# Si7020-A10_-_czujnik_wilgotno_ci.net
KiCad netlist of a schematic drawn in EAGLE
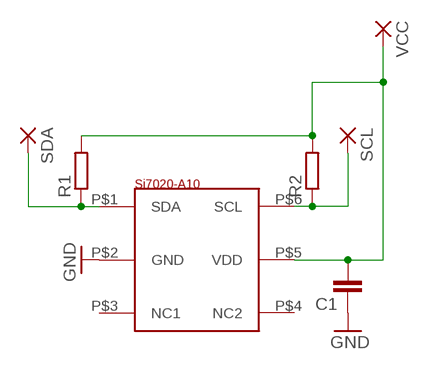
[diagram p0: schematic, sheet 1]

(export (version "E")
  (design (tool "Eeschema 10.0.6"))
  (components
    (comp (ref "C1")
      (value "C-EUC0805")
      (footprint "eagle-import:C0805")
      (libsource (lib "eagle-import") (part "C-EUC0805"))
    )
    (comp (ref "R1")
      (value "R-EU_M0805")
      (footprint "eagle-import:M0805")
      (libsource (lib "eagle-import") (part "R-EU_M0805"))
    )
    (comp (ref "R2")
      (value "R-EU_M0805")
      (footprint "eagle-import:M0805")
      (libsource (lib "eagle-import") (part "R-EU_M0805"))
    )
    (comp (ref "SCL")
      (value "2,54/0,9")
      (footprint "eagle-import:2,54_0,9")
      (libsource (lib "eagle-import") (part "2,54/0,9"))
    )
    (comp (ref "SDA")
      (value "2,54/0,9")
      (footprint "eagle-import:2,54_0,9")
      (libsource (lib "eagle-import") (part "2,54/0,9"))
    )
    (comp (ref "U$1")
      (value "SI7020-A10")
      (footprint "eagle-import:DFN6(3X3MM)")
      (libsource (lib "eagle-import") (part "SI7020-A10"))
    )
    (comp (ref "VCC")
      (value "2,54/0,9")
      (footprint "eagle-import:2,54_0,9")
      (libsource (lib "eagle-import") (part "2,54/0,9"))
    )
  )
  (nets
    (net (code "1") (name "GND") (class "Default")
      (node (ref "C1") (pin "1") (pinfunction "1_1") (pintype "passive"))
      (node (ref "U$1") (pin "P$2") (pinfunction "GND_P$2") (pintype "bidirectional"))
    )
    (net (code "2") (name "Net-(SCL-P)") (class "Default")
      (node (ref "R2") (pin "1") (pinfunction "1_1") (pintype "passive"))
      (node (ref "SCL") (pin "1") (pinfunction "P_1") (pintype "passive"))
      (node (ref "U$1") (pin "P$6") (pinfunction "SCL_P$6") (pintype "bidirectional"))
    )
    (net (code "3") (name "Net-(SDA-P)") (class "Default")
      (node (ref "R1") (pin "1") (pinfunction "1_1") (pintype "passive"))
      (node (ref "SDA") (pin "1") (pinfunction "P_1") (pintype "passive"))
      (node (ref "U$1") (pin "P$1") (pinfunction "SDA_P$1") (pintype "bidirectional"))
    )
    (net (code "4") (name "Net-(U$1-VDD)") (class "Default")
      (node (ref "C1") (pin "2") (pinfunction "2_2") (pintype "passive"))
      (node (ref "R1") (pin "2") (pinfunction "2_2") (pintype "passive"))
      (node (ref "R2") (pin "2") (pinfunction "2_2") (pintype "passive"))
      (node (ref "U$1") (pin "P$5") (pinfunction "VDD_P$5") (pintype "bidirectional"))
      (node (ref "VCC") (pin "1") (pinfunction "P_1") (pintype "passive"))
    )
    (net (code "5") (name "unconnected-(U$1-NC1-PadP$3)") (class "Default")
      (node (ref "U$1") (pin "P$3") (pinfunction "NC1_P$3") (pintype "bidirectional"))
    )
    (net (code "6") (name "unconnected-(U$1-NC2-PadP$4)") (class "Default")
      (node (ref "U$1") (pin "P$4") (pinfunction "NC2_P$4") (pintype "bidirectional"))
    )
  )
)
